# 01_ESP-CAM.net
KiCad netlist of a schematic drawn in Altium Designer
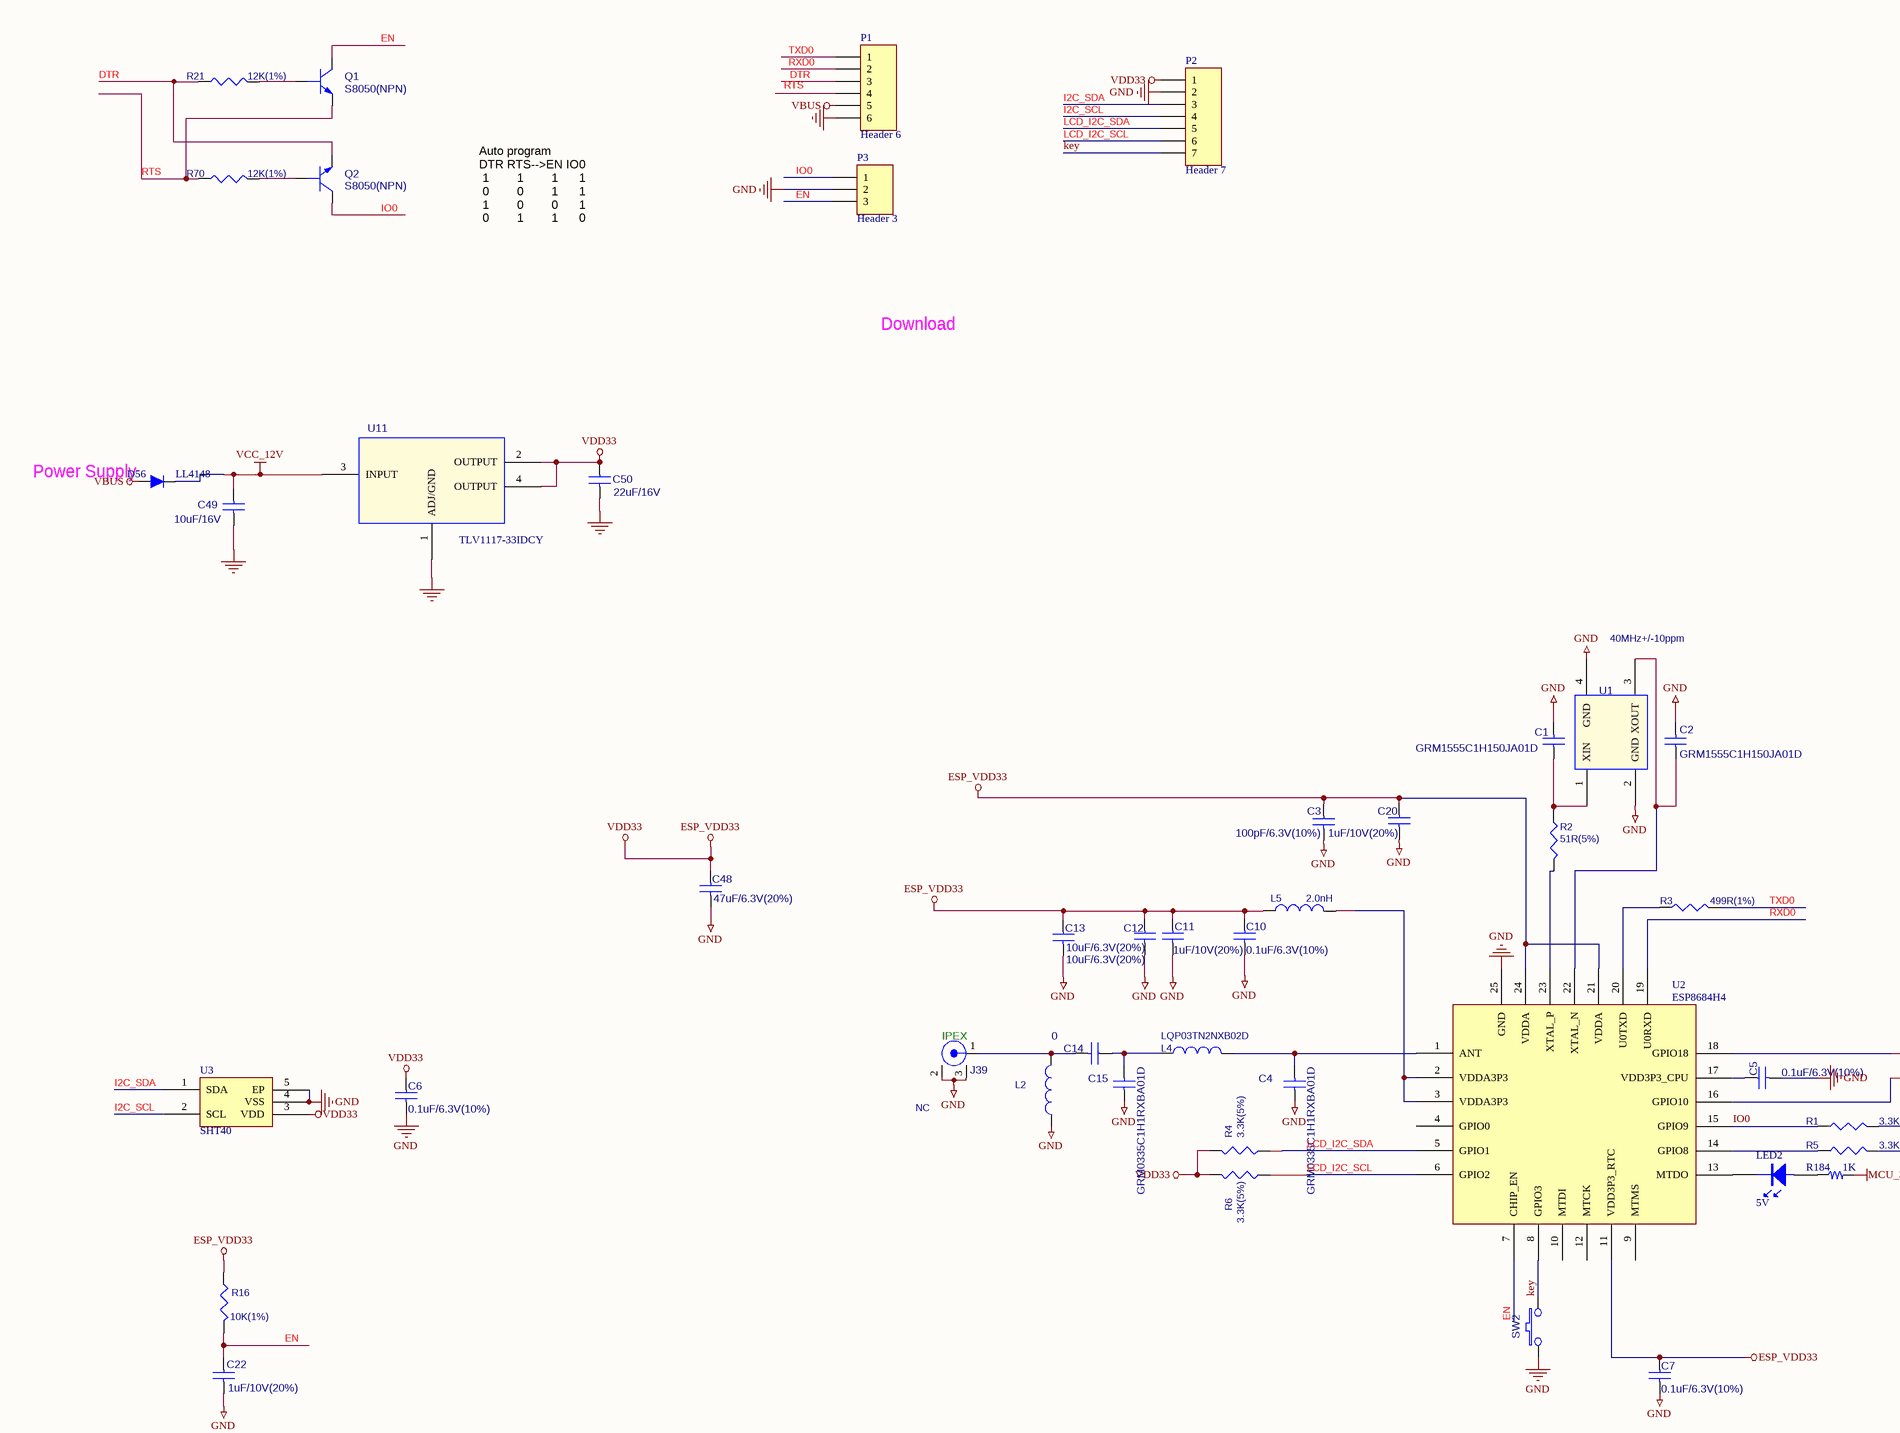
[diagram p0: 01_ESP-CAM.SchDoc, top left]
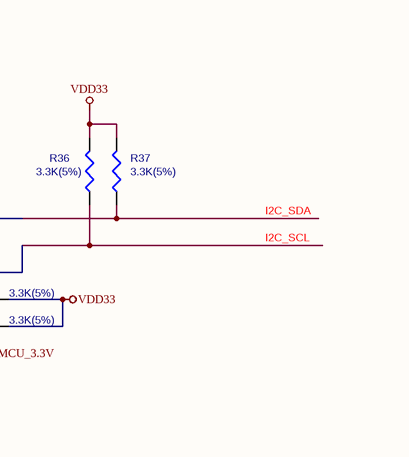
[diagram p1: 01_ESP-CAM.SchDoc, top right]
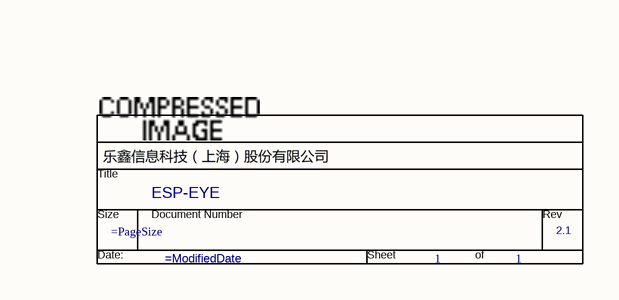
[diagram p2: 01_ESP-CAM.SchDoc, bottom right]

(export (version "E")
  (design (tool "Eeschema 10.0.6"))
  (components
    (comp (ref "*")
      (value "~")
      (fields
        (field (name "REVCODE") "2.1")
        (field (name "TITLE") "ESP-EYE")
        (field (name "PAGE NUMBER") "1")
        (field (name "PAGE COUNT") "1")
      )
      (libsource (lib "*") (part "espTitleBlock1"))
    )
    (comp (ref "C1")
      (value "GRM1555C1H150JA01D")
      (footprint "0402C")
      (fields (field (name "Comment") "CAP NP_Dup1"))
      (libsource (lib "*") (part "CAP NP_Dup1"))
    )
    (comp (ref "C2")
      (value "GRM1555C1H150JA01D")
      (footprint "0402C")
      (fields (field (name "Comment") "CAP NP_Dup1"))
      (libsource (lib "*") (part "CAP NP_Dup1"))
    )
    (comp (ref "C3")
      (value "100pF/6.3V(10%)")
      (footprint "0402C")
      (fields (field (name "Comment") "CAP NP_Dup1"))
      (libsource (lib "*") (part "CAP NP_Dup1"))
    )
    (comp (ref "C4")
      (value "GRM0335C1H1RXBA01D")
      (footprint "0402C")
      (fields (field (name "Comment") "CAP NP_Dup1"))
      (libsource (lib "*") (part "CAP NP_Dup1"))
    )
    (comp (ref "C5")
      (value "0.1uF/6.3V(10%)")
      (footprint "0402C")
      (fields (field (name "Comment") "CAP NP_Dup1"))
      (libsource (lib "*") (part "CAP NP_Dup1"))
    )
    (comp (ref "C6")
      (value "0.1uF/6.3V(10%)")
      (footprint "0402C")
      (fields (field (name "Comment") "CAP NP_Dup1"))
      (libsource (lib "*") (part "CAP NP_Dup1"))
    )
    (comp (ref "C7")
      (value "0.1uF/6.3V(10%)")
      (footprint "0402C")
      (fields (field (name "Comment") "CAP NP_Dup1"))
      (libsource (lib "*") (part "CAP NP_Dup1"))
    )
    (comp (ref "C10")
      (value "0.1uF/6.3V(10%)")
      (footprint "0402C")
      (fields (field (name "Comment") "CAP NP_Dup1"))
      (libsource (lib "*") (part "CAP NP_Dup1"))
    )
    (comp (ref "C11")
      (value "1uF/10V(20%)")
      (footprint "0402C")
      (fields (field (name "Comment") "CAP NP_Dup1"))
      (libsource (lib "*") (part "CAP NP_Dup1"))
    )
    (comp (ref "C12")
      (value "10uF/6.3V(20%)")
      (footprint "0402C")
      (fields (field (name "Comment") "CAP NP_Dup1"))
      (libsource (lib "*") (part "CAP NP_Dup1"))
    )
    (comp (ref "C13")
      (value "10uF/6.3V(20%)")
      (footprint "0402C")
      (fields (field (name "Comment") "CAP NP_Dup1"))
      (libsource (lib "*") (part "CAP NP_Dup1"))
    )
    (comp (ref "C14")
      (value "0")
      (footprint "0402C")
      (fields (field (name "Comment") "CAP NP_Dup1"))
      (libsource (lib "*") (part "CAP NP_Dup1"))
    )
    (comp (ref "C15")
      (value "GRM0335C1H1RXBA01D")
      (footprint "0402C")
      (fields (field (name "Comment") "CAP NP_Dup1"))
      (libsource (lib "*") (part "CAP NP_Dup1"))
    )
    (comp (ref "C20")
      (value "1uF/10V(20%)")
      (footprint "0402C")
      (fields (field (name "Comment") "CAP NP_Dup1"))
      (libsource (lib "*") (part "CAP NP_Dup1"))
    )
    (comp (ref "C22")
      (value "1uF/10V(20%)")
      (footprint "0402C")
      (fields (field (name "Comment") "CAP NP_Dup1"))
      (libsource (lib "*") (part "CAP NP_Dup1"))
    )
    (comp (ref "C48")
      (value "47uF/6.3V(20%)")
      (footprint "1206C")
      (fields (field (name "Comment") "CAP NP_Dup1"))
      (libsource (lib "*") (part "CAP NP_Dup1"))
    )
    (comp (ref "C49")
      (value "10uF/16V")
      (footprint "0603C")
      (fields (field (name "Comment") "CAP NP"))
      (libsource (lib "*") (part "CAP NP"))
    )
    (comp (ref "C50")
      (value "22uF/16V")
      (footprint "1206C")
      (fields (field (name "Comment") "CAP NP"))
      (libsource (lib "*") (part "CAP NP"))
    )
    (comp (ref "D56")
      (value "LL4148")
      (footprint "sod123")
      (description "VISHAY,LL4148,圆柱体MiniMELF100V/2A,ROHS")
      (libsource (lib "Device2018") (part "LL4148"))
    )
    (comp (ref "J39")
      (value "IPEX")
      (footprint "ANT_UFL_R_SMT")
      (fields (field (name "Comment") "IPEX_0"))
      (libsource (lib "*") (part "IPEX_0"))
    )
    (comp (ref "L2")
      (value "NC")
      (footprint "0402R")
      (fields (field (name "Comment") "CHOKE"))
      (libsource (lib "") (part "CHOKE_1"))
    )
    (comp (ref "L4")
      (value "LQP03TN2NXB02D")
      (footprint "0402R")
      (fields (field (name "Comment") "CHOKE"))
      (libsource (lib "*") (part "CHOKE"))
    )
    (comp (ref "L5")
      (value "2.0nH")
      (footprint "0402R")
      (fields (field (name "Comment") "CHOKE"))
      (libsource (lib "") (part "CHOKE_1"))
    )
    (comp (ref "LED2") (value "5V") (footprint "0603LED") (libsource (lib "*") (part "LED")))
    (comp (ref "P1")
      (value "Header 6")
      (footprint "HDR1X6")
      (description "Header, 6-Pin")
      (fields (field (name "PUBLISHER") "Altium Limited"))
      (libsource (lib "Miscellaneous Connectors") (part "Header 6"))
    )
    (comp (ref "P2")
      (value "Header 7")
      (footprint "HDR1X7")
      (description "Header, 7-Pin")
      (fields (field (name "PUBLISHER") "Altium Limited"))
      (libsource (lib "Miscellaneous Connectors") (part "Header 7"))
    )
    (comp (ref "P3")
      (value "Header 3")
      (footprint "HDR1X3")
      (description "Header, 3-Pin")
      (fields (field (name "PUBLISHER") "Altium Limited"))
      (libsource (lib "Miscellaneous Connectors") (part "Header 3"))
    )
    (comp (ref "Q1")
      (value "S8050(NPN)")
      (footprint "SOT23-3")
      (fields (field (name "Comment") "NPN BCE_2"))
      (libsource (lib "*") (part "NPN BCE_2"))
    )
    (comp (ref "Q2")
      (value "S8050(NPN)")
      (footprint "SOT23-3")
      (fields (field (name "Comment") "NPN BCE_2"))
      (libsource (lib "*") (part "NPN BCE_2"))
    )
    (comp (ref "R1")
      (value "3.3K(5%)")
      (footprint "0402R")
      (fields (field (name "Comment") "RESISTOR_0"))
      (libsource (lib "*") (part "RESISTOR_0"))
    )
    (comp (ref "R2")
      (value "51R(5%)")
      (footprint "0402R")
      (fields (field (name "Comment") "RESISTOR"))
      (libsource (lib "*") (part "RESISTOR"))
    )
    (comp (ref "R3")
      (value "499R(1%)")
      (footprint "0402R")
      (fields (field (name "Comment") "RESISTOR"))
      (libsource (lib "*") (part "RESISTOR"))
    )
    (comp (ref "R4")
      (value "3.3K(5%)")
      (footprint "0402R")
      (fields (field (name "Comment") "RESISTOR_0"))
      (libsource (lib "*") (part "RESISTOR_0"))
    )
    (comp (ref "R5")
      (value "3.3K(5%)")
      (footprint "0402R")
      (fields (field (name "Comment") "RESISTOR_0"))
      (libsource (lib "*") (part "RESISTOR_0"))
    )
    (comp (ref "R6")
      (value "3.3K(5%)")
      (footprint "0402R")
      (fields (field (name "Comment") "RESISTOR_0"))
      (libsource (lib "*") (part "RESISTOR_0"))
    )
    (comp (ref "R16")
      (value "10K(1%)")
      (footprint "0402R")
      (fields (field (name "Comment") "RESISTOR_0"))
      (libsource (lib "*") (part "RESISTOR_0"))
    )
    (comp (ref "R21")
      (value "12K(1%)")
      (footprint "0402R")
      (fields (field (name "Comment") "RESISTOR_0"))
      (libsource (lib "*") (part "RESISTOR_0"))
    )
    (comp (ref "R36")
      (value "3.3K(5%)")
      (footprint "0402R")
      (fields (field (name "Comment") "RESISTOR_0"))
      (libsource (lib "*") (part "RESISTOR_0"))
    )
    (comp (ref "R37")
      (value "3.3K(5%)")
      (footprint "0402R")
      (fields (field (name "Comment") "RESISTOR_0"))
      (libsource (lib "*") (part "RESISTOR_0"))
    )
    (comp (ref "R70")
      (value "12K(1%)")
      (footprint "0402R")
      (fields (field (name "Comment") "RESISTOR_0"))
      (libsource (lib "*") (part "RESISTOR_0"))
    )
    (comp (ref "R184")
      (value "1K")
      (footprint "0603R")
      (description "R")
      (libsource (lib "JRJ_1") (part "R"))
    )
    (comp (ref "SW2")
      (value "SW PUSHBUTTON")
      (footprint "KEY_3X6")
      (libsource (lib "*") (part "SW PUSHBUTTON"))
    )
    (comp (ref "U1")
      (value "40MHz+/-10ppm")
      (footprint "CRY_3225")
      (fields (field (name "Comment") "X1_1"))
      (libsource (lib "*") (part "X1_1"))
    )
    (comp (ref "U2")
      (value "ESP8684H4")
      (footprint "QFN24-MPU6000")
      (libsource (lib "Schlib_20110825") (part "ESP8684H4"))
    )
    (comp (ref "U3") (value "SHT40") (libsource (lib "Schlib_20110825") (part "SHT40")))
    (comp (ref "U11")
      (value "TLV1117-33IDCY")
      (footprint "SOT223")
      (fields (field (name "Comment") "TLV1117"))
      (libsource (lib "*") (part "TLV1117-33IDCY"))
    )
  )
  (nets
    (net (code "1") (name "/DTR") (class "Default")
      (node (ref "P1") (pin "3") (pinfunction "3_3") (pintype "passive"))
      (node (ref "Q2") (pin "2") (pinfunction "E_2") (pintype "passive"))
      (node (ref "R21") (pin "1") (pinfunction "1_1") (pintype "passive"))
    )
    (net (code "2") (name "/EN") (class "Default")
      (node (ref "C22") (pin "1") (pinfunction "1_1") (pintype "passive"))
      (node (ref "P3") (pin "3") (pinfunction "3_3") (pintype "passive"))
      (node (ref "Q1") (pin "3") (pinfunction "C_3") (pintype "passive"))
      (node (ref "R16") (pin "2") (pinfunction "2_2") (pintype "passive"))
      (node (ref "U2") (pin "7") (pinfunction "CHIP_EN_7") (pintype "passive"))
    )
    (net (code "3") (name "/I2C_SCL") (class "Default")
      (node (ref "P2") (pin "4") (pinfunction "4_4") (pintype "passive"))
      (node (ref "R36") (pin "1") (pinfunction "1_1") (pintype "passive"))
      (node (ref "U2") (pin "16") (pinfunction "GPIO10_16") (pintype "passive"))
      (node (ref "U3") (pin "2") (pinfunction "SCL_2") (pintype "passive"))
    )
    (net (code "4") (name "/I2C_SDA") (class "Default")
      (node (ref "P2") (pin "3") (pinfunction "3_3") (pintype "passive"))
      (node (ref "R37") (pin "1") (pinfunction "1_1") (pintype "passive"))
      (node (ref "U2") (pin "18") (pinfunction "GPIO18_18") (pintype "passive"))
      (node (ref "U3") (pin "1") (pinfunction "SDA_1") (pintype "passive"))
    )
    (net (code "5") (name "/IO0") (class "Default")
      (node (ref "P3") (pin "1") (pinfunction "1_1") (pintype "passive"))
      (node (ref "Q2") (pin "3") (pinfunction "C_3") (pintype "passive"))
      (node (ref "R1") (pin "1") (pinfunction "1_1") (pintype "passive"))
      (node (ref "U2") (pin "15") (pinfunction "GPIO9_15") (pintype "passive"))
    )
    (net (code "6") (name "/LCD_I2C_SCL") (class "Default")
      (node (ref "P2") (pin "6") (pinfunction "6_6") (pintype "passive"))
      (node (ref "R6") (pin "1") (pinfunction "1_1") (pintype "passive"))
      (node (ref "U2") (pin "6") (pinfunction "GPIO2_6") (pintype "passive"))
    )
    (net (code "7") (name "/LCD_I2C_SDA") (class "Default")
      (node (ref "P2") (pin "5") (pinfunction "5_5") (pintype "passive"))
      (node (ref "R4") (pin "1") (pinfunction "1_1") (pintype "passive"))
      (node (ref "U2") (pin "5") (pinfunction "GPIO1_5") (pintype "passive"))
    )
    (net (code "8") (name "/RTS") (class "Default")
      (node (ref "Q1") (pin "2") (pinfunction "E_2") (pintype "passive"))
      (node (ref "R70") (pin "1") (pinfunction "1_1") (pintype "passive"))
    )
    (net (code "9") (name "/RXD0") (class "Default")
      (node (ref "P1") (pin "2") (pinfunction "2_2") (pintype "passive"))
      (node (ref "U2") (pin "19") (pinfunction "U0RXD_19") (pintype "passive"))
    )
    (net (code "10") (name "/TXD0") (class "Default")
      (node (ref "P1") (pin "1") (pinfunction "1_1") (pintype "passive"))
      (node (ref "R3") (pin "2") (pinfunction "2_2") (pintype "passive"))
    )
    (net (code "11") (name "/key") (class "Default")
      (node (ref "P2") (pin "7") (pinfunction "7_7") (pintype "passive"))
      (node (ref "SW2") (pin "2") (pinfunction "2_2") (pintype "passive"))
      (node (ref "U2") (pin "8") (pinfunction "GPIO3_8") (pintype "passive"))
    )
    (net (code "12") (name "ESP_VDD33") (class "Default")
      (node (ref "C10") (pin "1") (pinfunction "1_1") (pintype "passive"))
      (node (ref "C11") (pin "1") (pinfunction "1_1") (pintype "passive"))
      (node (ref "C12") (pin "1") (pinfunction "1_1") (pintype "passive"))
      (node (ref "C13") (pin "1") (pinfunction "1_1") (pintype "passive"))
      (node (ref "C20") (pin "1") (pinfunction "1_1") (pintype "passive"))
      (node (ref "C3") (pin "1") (pinfunction "1_1") (pintype "passive"))
      (node (ref "C48") (pin "1") (pinfunction "1_1") (pintype "passive"))
      (node (ref "C50") (pin "1") (pinfunction "1_1") (pintype "passive"))
      (node (ref "C6") (pin "1") (pinfunction "1_1") (pintype "passive"))
      (node (ref "C7") (pin "1") (pinfunction "1_1") (pintype "passive"))
      (node (ref "L5") (pin "2") (pinfunction "2_2") (pintype "passive"))
      (node (ref "P2") (pin "1") (pinfunction "1_1") (pintype "passive"))
      (node (ref "R1") (pin "2") (pinfunction "2_2") (pintype "passive"))
      (node (ref "R16") (pin "1") (pinfunction "1_1") (pintype "passive"))
      (node (ref "R36") (pin "2") (pinfunction "2_2") (pintype "passive"))
      (node (ref "R37") (pin "2") (pinfunction "2_2") (pintype "passive"))
      (node (ref "R4") (pin "2") (pinfunction "2_2") (pintype "passive"))
      (node (ref "R5") (pin "2") (pinfunction "2_2") (pintype "passive"))
      (node (ref "R6") (pin "2") (pinfunction "2_2") (pintype "passive"))
      (node (ref "U11") (pin "2") (pinfunction "OUTPUT_2") (pintype "power_in"))
      (node (ref "U11") (pin "4") (pinfunction "OUTPUT_4") (pintype "power_in"))
      (node (ref "U2") (pin "11") (pinfunction "VDD3P3_RTC_11") (pintype "passive"))
      (node (ref "U2") (pin "21") (pinfunction "VDDA_21") (pintype "passive"))
      (node (ref "U2") (pin "24") (pinfunction "VDDA_24") (pintype "passive"))
      (node (ref "U3") (pin "3") (pinfunction "VDD_3") (pintype "passive"))
    )
    (net (code "13") (name "GND") (class "Default")
      (node (ref "C1") (pin "2") (pinfunction "2_2") (pintype "passive"))
      (node (ref "C10") (pin "2") (pinfunction "2_2") (pintype "passive"))
      (node (ref "C11") (pin "2") (pinfunction "2_2") (pintype "passive"))
      (node (ref "C12") (pin "2") (pinfunction "2_2") (pintype "passive"))
      (node (ref "C13") (pin "2") (pinfunction "2_2") (pintype "passive"))
      (node (ref "C15") (pin "1") (pinfunction "1_1") (pintype "passive"))
      (node (ref "C2") (pin "2") (pinfunction "2_2") (pintype "passive"))
      (node (ref "C20") (pin "2") (pinfunction "2_2") (pintype "passive"))
      (node (ref "C22") (pin "2") (pinfunction "2_2") (pintype "passive"))
      (node (ref "C3") (pin "2") (pinfunction "2_2") (pintype "passive"))
      (node (ref "C4") (pin "1") (pinfunction "1_1") (pintype "passive"))
      (node (ref "C48") (pin "2") (pinfunction "2_2") (pintype "passive"))
      (node (ref "C49") (pin "2") (pinfunction "2_2") (pintype "passive"))
      (node (ref "C5") (pin "2") (pinfunction "2_2") (pintype "passive"))
      (node (ref "C50") (pin "2") (pinfunction "2_2") (pintype "passive"))
      (node (ref "C6") (pin "2") (pinfunction "2_2") (pintype "passive"))
      (node (ref "C7") (pin "2") (pinfunction "2_2") (pintype "passive"))
      (node (ref "J39") (pin "2") (pinfunction "GND1_2") (pintype "passive"))
      (node (ref "J39") (pin "3") (pinfunction "GND2_3") (pintype "passive"))
      (node (ref "L2") (pin "2") (pinfunction "2_2") (pintype "passive"))
      (node (ref "P1") (pin "6") (pinfunction "6_6") (pintype "passive"))
      (node (ref "P2") (pin "2") (pinfunction "2_2") (pintype "passive"))
      (node (ref "P3") (pin "2") (pinfunction "2_2") (pintype "passive"))
      (node (ref "SW2") (pin "1") (pinfunction "1_1") (pintype "passive"))
      (node (ref "U1") (pin "2") (pinfunction "GND_2") (pintype "power_in"))
      (node (ref "U1") (pin "4") (pinfunction "GND_4") (pintype "power_in"))
      (node (ref "U11") (pin "1") (pinfunction "ADJ/GND_1") (pintype "passive"))
      (node (ref "U2") (pin "25") (pinfunction "GND_25") (pintype "passive"))
      (node (ref "U3") (pin "4") (pinfunction "VSS_4") (pintype "passive"))
      (node (ref "U3") (pin "5") (pinfunction "EP_5") (pintype "passive"))
    )
    (net (code "14") (name "MCU_3.3V") (class "Default") (node (ref "R184") (pin "2") (pintype "passive")))
    (net (code "15") (name "Net-(C14-Pad1)") (class "Default")
      (node (ref "C14") (pin "1") (pinfunction "1_1") (pintype "passive"))
      (node (ref "C15") (pin "2") (pinfunction "2_2") (pintype "passive"))
      (node (ref "L4") (pin "2") (pinfunction "2_2") (pintype "passive"))
    )
    (net (code "16") (name "Net-(J39-RF)") (class "Default")
      (node (ref "C14") (pin "2") (pinfunction "2_2") (pintype "passive"))
      (node (ref "J39") (pin "1") (pinfunction "RF_1") (pintype "passive"))
      (node (ref "L2") (pin "1") (pinfunction "1_1") (pintype "passive"))
    )
    (net (code "17") (name "Net-(L5-Pad1)") (class "Default")
      (node (ref "L5") (pin "1") (pinfunction "1_1") (pintype "passive"))
      (node (ref "U2") (pin "2") (pinfunction "VDDA3P3_2") (pintype "passive"))
      (node (ref "U2") (pin "3") (pinfunction "VDDA3P3_3") (pintype "passive"))
    )
    (net (code "18") (name "Net-(LED2-Pad1)") (class "Default")
      (node (ref "LED2") (pin "1") (pinfunction "1_1") (pintype "passive"))
      (node (ref "R184") (pin "1") (pintype "passive"))
    )
    (net (code "19") (name "Net-(Q1-B)") (class "Default")
      (node (ref "Q1") (pin "1") (pinfunction "B_1") (pintype "passive"))
      (node (ref "R21") (pin "2") (pinfunction "2_2") (pintype "passive"))
    )
    (net (code "20") (name "Net-(Q2-B)") (class "Default")
      (node (ref "Q2") (pin "1") (pinfunction "B_1") (pintype "passive"))
      (node (ref "R70") (pin "2") (pinfunction "2_2") (pintype "passive"))
    )
    (net (code "21") (name "Net-(U1-XIN)") (class "Default")
      (node (ref "C1") (pin "1") (pinfunction "1_1") (pintype "passive"))
      (node (ref "R2") (pin "1") (pinfunction "1_1") (pintype "passive"))
      (node (ref "U1") (pin "1") (pinfunction "XIN_1") (pintype "passive"))
    )
    (net (code "22") (name "Net-(U1-XOUT)") (class "Default")
      (node (ref "C2") (pin "1") (pinfunction "1_1") (pintype "passive"))
      (node (ref "U1") (pin "3") (pinfunction "XOUT_3") (pintype "passive"))
      (node (ref "U2") (pin "22") (pinfunction "XTAL_N_22") (pintype "passive"))
    )
    (net (code "23") (name "Net-(U2-ANT)") (class "Default")
      (node (ref "C4") (pin "2") (pinfunction "2_2") (pintype "passive"))
      (node (ref "L4") (pin "1") (pinfunction "1_1") (pintype "passive"))
      (node (ref "U2") (pin "1") (pinfunction "ANT_1") (pintype "passive"))
    )
    (net (code "24") (name "Net-(U2-GPIO8)") (class "Default")
      (node (ref "R5") (pin "1") (pinfunction "1_1") (pintype "passive"))
      (node (ref "U2") (pin "14") (pinfunction "GPIO8_14") (pintype "passive"))
    )
    (net (code "25") (name "Net-(U2-MTDO)") (class "Default")
      (node (ref "LED2") (pin "2") (pinfunction "2_2") (pintype "passive"))
      (node (ref "U2") (pin "13") (pinfunction "MTDO_13") (pintype "passive"))
    )
    (net (code "26") (name "Net-(U2-U0TXD)") (class "Default")
      (node (ref "R3") (pin "1") (pinfunction "1_1") (pintype "passive"))
      (node (ref "U2") (pin "20") (pinfunction "U0TXD_20") (pintype "passive"))
    )
    (net (code "27") (name "Net-(U2-VDD3P3_CPU)") (class "Default")
      (node (ref "C5") (pin "1") (pinfunction "1_1") (pintype "passive"))
      (node (ref "U2") (pin "17") (pinfunction "VDD3P3_CPU_17") (pintype "passive"))
    )
    (net (code "28") (name "Net-(U2-XTAL_P)") (class "Default")
      (node (ref "R2") (pin "2") (pinfunction "2_2") (pintype "passive"))
      (node (ref "U2") (pin "23") (pinfunction "XTAL_P_23") (pintype "passive"))
    )
    (net (code "29") (name "VBUS") (class "Default")
      (node (ref "D56") (pin "2") (pinfunction "2_2") (pintype "passive"))
      (node (ref "P1") (pin "5") (pinfunction "5_5") (pintype "passive"))
    )
    (net (code "30") (name "VCC_12V") (class "Default")
      (node (ref "C49") (pin "1") (pinfunction "1_1") (pintype "passive"))
      (node (ref "D56") (pin "1") (pinfunction "1_1") (pintype "passive"))
      (node (ref "U11") (pin "3") (pinfunction "INPUT_3") (pintype "passive"))
    )
    (net (code "31") (name "unconnected-(P1-Pad4)") (class "Default")
      (node (ref "P1") (pin "4") (pinfunction "4_4") (pintype "passive"))
    )
    (net (code "32") (name "unconnected-(U2-GPIO0-Pad4)") (class "Default")
      (node (ref "U2") (pin "4") (pinfunction "GPIO0_4") (pintype "passive"))
    )
    (net (code "33") (name "unconnected-(U2-MTCK-Pad12)") (class "Default")
      (node (ref "U2") (pin "12") (pinfunction "MTCK_12") (pintype "passive"))
    )
    (net (code "34") (name "unconnected-(U2-MTDI-Pad10)") (class "Default")
      (node (ref "U2") (pin "10") (pinfunction "MTDI_10") (pintype "passive"))
    )
    (net (code "35") (name "unconnected-(U2-MTMS-Pad9)") (class "Default")
      (node (ref "U2") (pin "9") (pinfunction "MTMS_9") (pintype "passive"))
    )
  )
)
